# LAUNCHPAD.net
KiCad netlist of a schematic drawn in Altium Designer
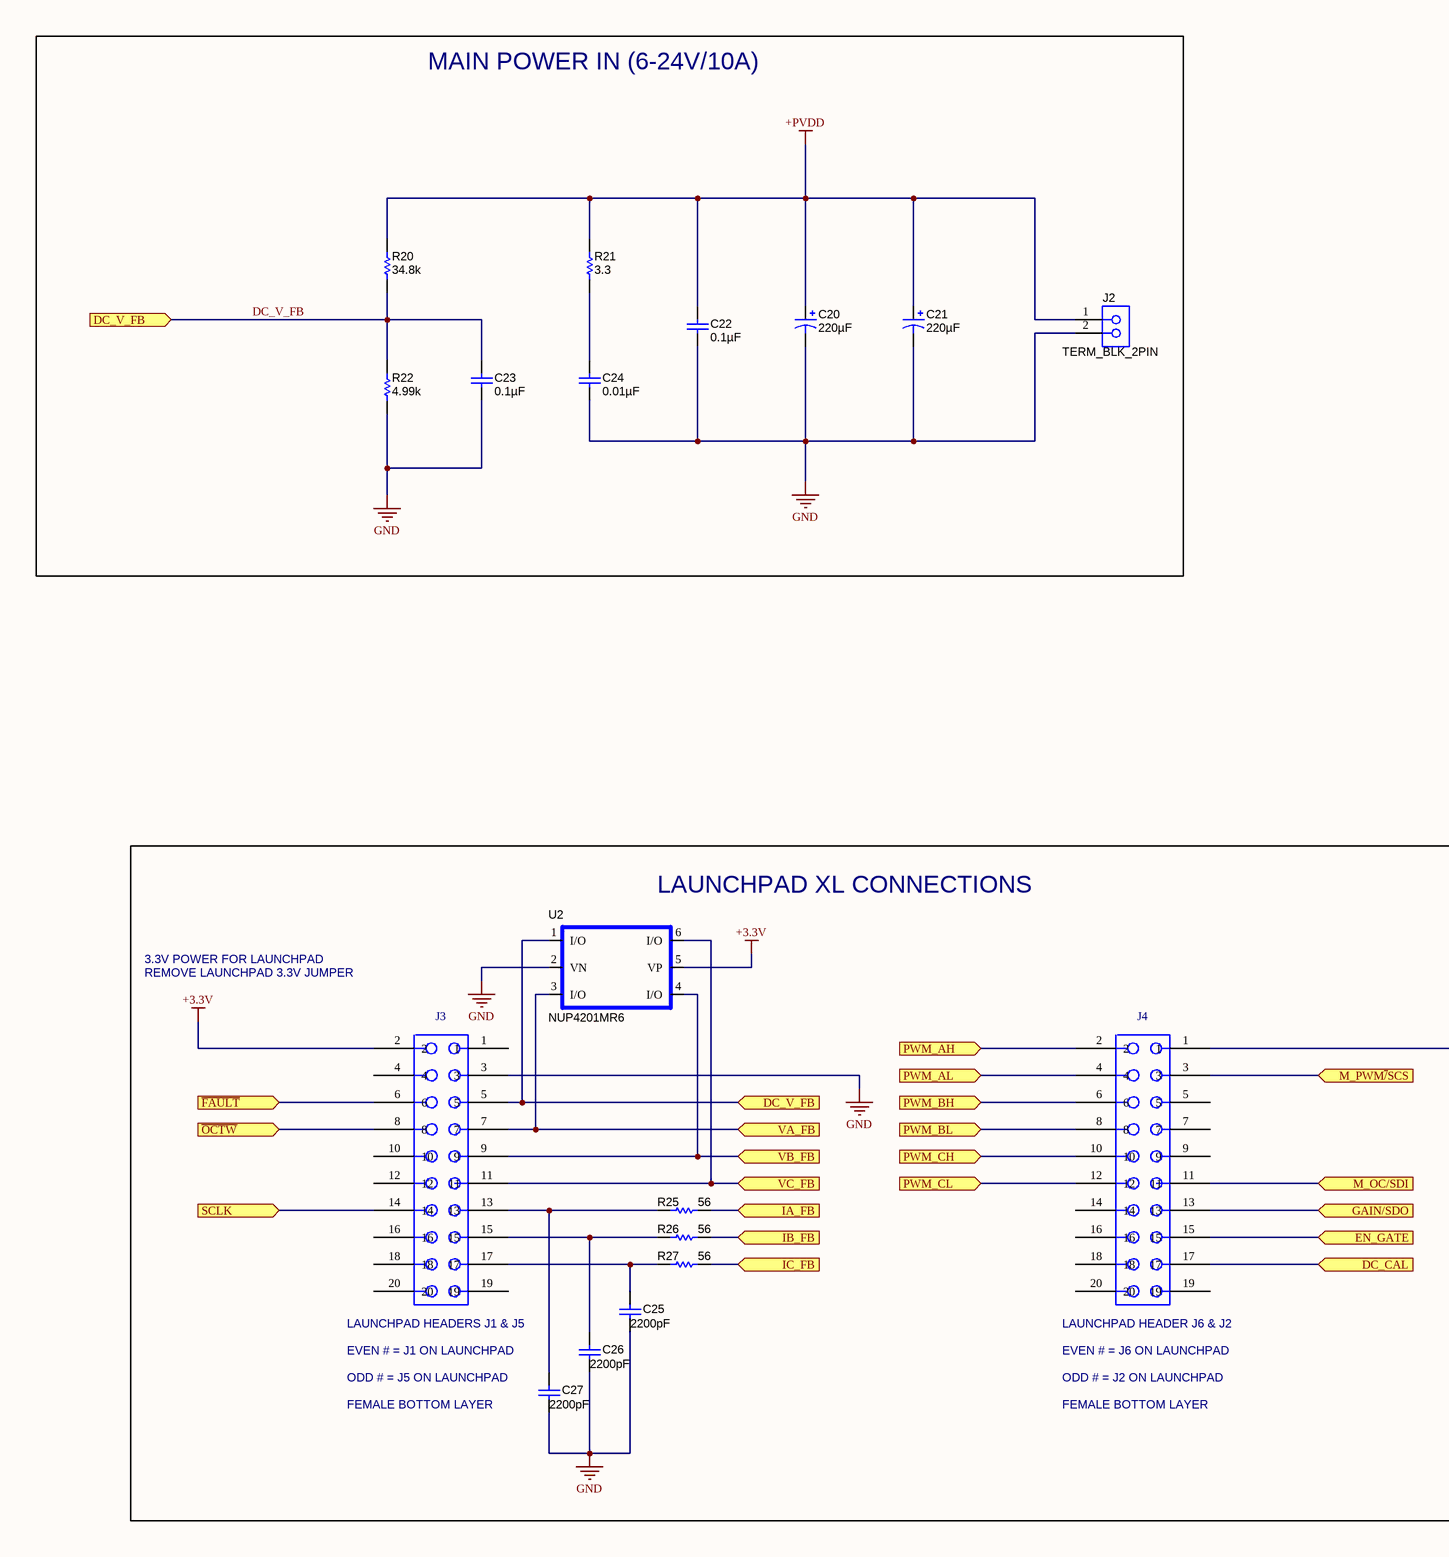
[diagram p0: LAUNCHPAD.SchDoc, left]
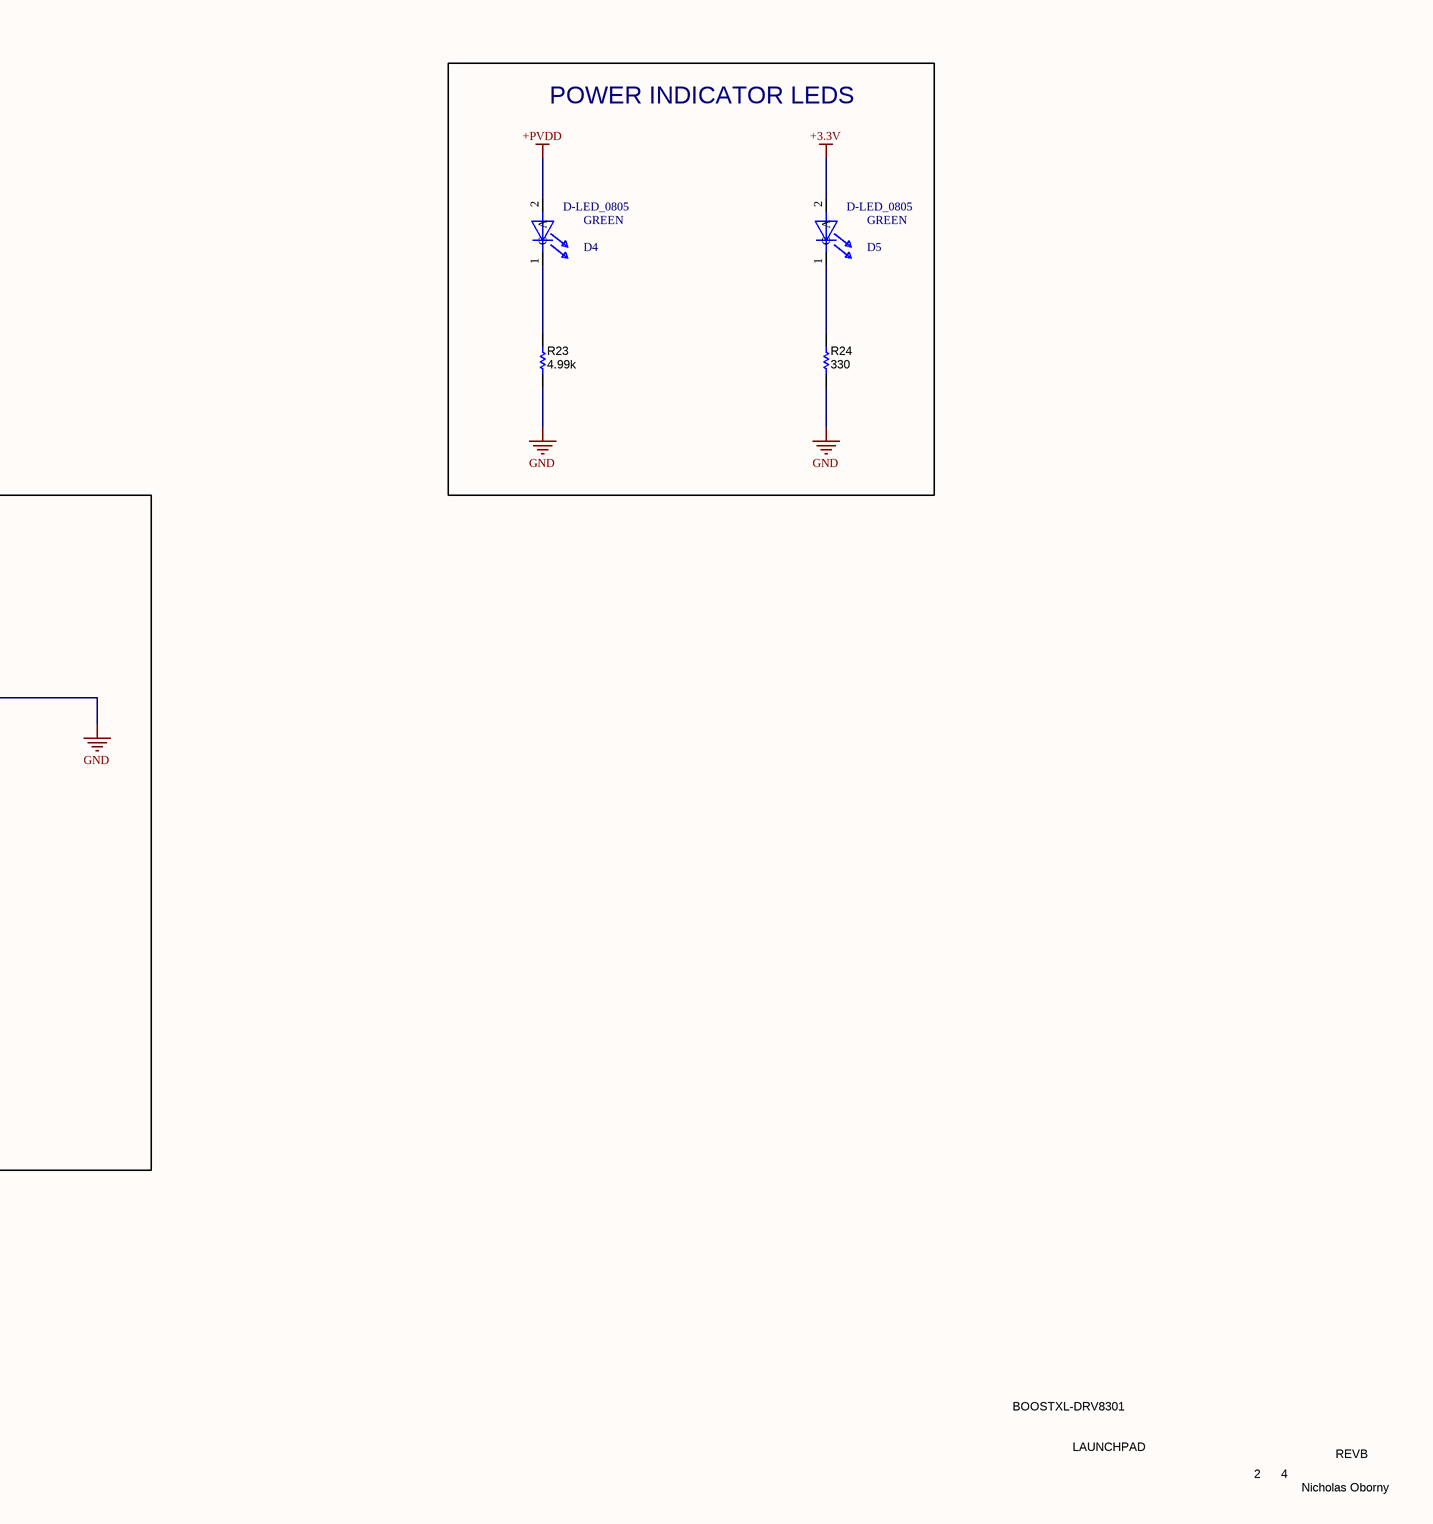
[diagram p1: LAUNCHPAD.SchDoc, right]

(export (version "E")
  (design (tool "Eeschema 10.0.6"))
  (components
    (comp (ref "C20")
      (value "EEE-FC1H221P")
      (footprint "SM_RADIAL_G")
      (description "CAP, AL, 220uF, 50V, +/-20%, 0.3 ohm, SMD")
      (fields
        (field (name "VALUEDISPLAYED") "220µF")
        (field (name "MANUFACTURER") "Panasonic")
        (field (name "PUBLISHER") "Texas Instruments")
      )
      (libsource (lib "Capacitor_Aluminum") (part "EEE-FC1H221P"))
    )
    (comp (ref "C21")
      (value "EEE-FC1H221P")
      (footprint "SM_RADIAL_G")
      (description "CAP, AL, 220uF, 50V, +/-20%, 0.3 ohm, SMD")
      (fields
        (field (name "VALUEDISPLAYED") "220µF")
        (field (name "MANUFACTURER") "Panasonic")
        (field (name "PUBLISHER") "Texas Instruments")
      )
      (libsource (lib "Capacitor_Aluminum") (part "EEE-FC1H221P"))
    )
    (comp (ref "C22")
      (value "GRM188R72A104KA35D")
      (footprint "0603L")
      (description "CAP, CERM, 0.1uF, 100V, +/-10%, X7R, 0603")
      (fields
        (field (name "VALUEDISPLAYED") "0.1µF")
        (field (name "MANUFACTURER") "MuRata")
        (field (name "PUBLISHER") "Texas Instruments")
      )
      (libsource (lib "Capacitor_Ceramic") (part "GRM188R72A104KA35D"))
    )
    (comp (ref "C23")
      (value "C0603C104J4RACTU")
      (footprint "0603L")
      (description "CAP, CERM, 0.1uF, 16V, +/-5%, X7R, 0603")
      (fields
        (field (name "VALUEDISPLAYED") "0.1µF")
        (field (name "MANUFACTURER") "Kemet")
        (field (name "PUBLISHER") "Texas Instruments")
      )
      (libsource (lib "Capacitor_Ceramic") (part "C0603C104J4RACTU"))
    )
    (comp (ref "C24")
      (value "C1608X7R2A103K")
      (footprint "0603L")
      (description "CAP, CERM, 0.01uF, 100V, +/-10%, X7R, 0603")
      (fields
        (field (name "VALUEDISPLAYED") "0.01µF")
        (field (name "MANUFACTURER") "TDK")
        (field (name "PUBLISHER") "Texas Instruments")
      )
      (libsource (lib "Capacitor_Ceramic") (part "C1608X7R2A103K"))
    )
    (comp (ref "C25")
      (value "GRM188R71C222KA01D")
      (footprint "0603L")
      (description "CAP, CERM, 2200pF, 16V, +/-10%, X7R, 0603")
      (fields
        (field (name "VALUEDISPLAYED") "2200pF")
        (field (name "MANUFACTURER") "MuRata")
        (field (name "PUBLISHER") "Texas Instruments")
      )
      (libsource (lib "Capacitor_Ceramic") (part "GRM188R71C222KA01D"))
    )
    (comp (ref "C26")
      (value "GRM188R71C222KA01D")
      (footprint "0603L")
      (description "CAP, CERM, 2200pF, 16V, +/-10%, X7R, 0603")
      (fields
        (field (name "VALUEDISPLAYED") "2200pF")
        (field (name "MANUFACTURER") "MuRata")
        (field (name "PUBLISHER") "Texas Instruments")
      )
      (libsource (lib "Capacitor_Ceramic") (part "GRM188R71C222KA01D"))
    )
    (comp (ref "C27")
      (value "GRM188R71C222KA01D")
      (footprint "0603L")
      (description "CAP, CERM, 2200pF, 16V, +/-10%, X7R, 0603")
      (fields
        (field (name "VALUEDISPLAYED") "2200pF")
        (field (name "MANUFACTURER") "MuRata")
        (field (name "PUBLISHER") "Texas Instruments")
      )
      (libsource (lib "Capacitor_Ceramic") (part "GRM188R71C222KA01D"))
    )
    (comp (ref "D4")
      (value "D-LED_0805")
      (footprint "LED_0805")
      (description "LED THIN 565NM GRN DIFF 0805 SMD")
      (fields
        (field (name "PARTNUMBER") "SML-LXT0805GW-TR")
        (field (name "ALTIUM_VALUE") "GREEN")
        (field (name "MANUFACTURER") "Lumex Opto/Components Inc")
      )
      (libsource (lib "*") (part "D-LED_0805"))
    )
    (comp (ref "D5")
      (value "D-LED_0805")
      (footprint "LED_0805")
      (description "LED THIN 565NM GRN DIFF 0805 SMD")
      (fields
        (field (name "PARTNUMBER") "SML-LXT0805GW-TR")
        (field (name "ALTIUM_VALUE") "GREEN")
        (field (name "MANUFACTURER") "Lumex Opto/Components Inc")
      )
      (libsource (lib "*") (part "D-LED_0805"))
    )
    (comp (ref "J2")
      (value "TERM_BLK_2PIN")
      (footprint "CONN_ED120-2DS")
      (description "TERMINAL BLOCK 5.08MM VERT 2POS")
      (fields
        (field (name "PARTNUMBER") "OSTTA024163")
        (field (name "MANUFACTURER") "On-Shore Technology")
        (field (name "PUBLISHER") "Texas Instruments")
      )
      (libsource (lib "Connectors") (part "ED120/2DS"))
    )
    (comp (ref "J3")
      (value "HEADER_NPTC202KFM")
      (description "CONN RCPT 20POS .100 DL STR SMD")
      (fields (field (name "PARTNUMBER") "89898-310ALF") (field (name "MANUFACTURER") "FCI"))
      (libsource (lib "*") (part "HEADER_NPTC202KFM"))
    )
    (comp (ref "J4")
      (value "HEADER_NPTC202KFM")
      (description "CONN RCPT 20POS .100 DL STR SMD")
      (fields (field (name "PARTNUMBER") "89898-310ALF") (field (name "MANUFACTURER") "FCI"))
      (libsource (lib "*") (part "HEADER_NPTC202KFM"))
    )
    (comp (ref "R20")
      (value "34.8k")
      (footprint "0603L")
      (description "RES, 34.8k ohm, 1%, 0.1W, 0603")
      (fields
        (field (name "PARTNUMBER") "CRCW060334K8FKEA")
        (field (name "MANUFACTURER") "Vishay-Dale")
        (field (name "PUBLISHER") "Texas Instruments")
      )
      (libsource (lib "Resistor_0603") (part "CRCW060334K8FKEA"))
    )
    (comp (ref "R21")
      (value "3.3")
      (footprint "1206L")
      (description "RES, 3.3 ohm, 5%, 0.25W, 1206")
      (fields
        (field (name "PARTNUMBER") "CRCW12063R30JNEA")
        (field (name "MANUFACTURER") "Vishay-Dale")
        (field (name "PUBLISHER") "Texas Instruments")
      )
      (libsource (lib "Resistor_1206") (part "CRCW12063R30JNEA"))
    )
    (comp (ref "R22")
      (value "4.99k")
      (footprint "0603L")
      (description "RES, 4.99k ohm, 1%, 0.1W, 0603")
      (fields
        (field (name "PARTNUMBER") "CRCW06034K99FKEA")
        (field (name "MANUFACTURER") "Vishay-Dale")
        (field (name "PUBLISHER") "Texas Instruments")
      )
      (libsource (lib "Resistor_0603") (part "CRCW06034K99FKEA"))
    )
    (comp (ref "R23")
      (value "4.99k")
      (footprint "0603L")
      (description "RES, 4.99k ohm, 1%, 0.1W, 0603")
      (fields
        (field (name "PARTNUMBER") "CRCW06034K99FKEA")
        (field (name "MANUFACTURER") "Vishay-Dale")
        (field (name "PUBLISHER") "Texas Instruments")
      )
      (libsource (lib "Resistor_0603") (part "CRCW06034K99FKEA"))
    )
    (comp (ref "R24")
      (value "330")
      (footprint "0603L")
      (description "RES, 330 ohm, 5%, 0.1W, 0603")
      (fields
        (field (name "PARTNUMBER") "CRCW0603330RJNEA")
        (field (name "MANUFACTURER") "Vishay-Dale")
        (field (name "PUBLISHER") "Texas Instruments")
      )
      (libsource (lib "Resistor_0603") (part "CRCW0603330RJNEA"))
    )
    (comp (ref "R25")
      (value "56")
      (footprint "0603L")
      (description "RES, 56 ohm, 5%, 0.1W, 0603")
      (fields
        (field (name "PARTNUMBER") "CRCW060356R0JNEA")
        (field (name "MANUFACTURER") "Vishay-Dale")
        (field (name "PUBLISHER") "Texas Instruments")
      )
      (libsource (lib "Resistor_0603") (part "CRCW060356R0JNEA"))
    )
    (comp (ref "R26")
      (value "56")
      (footprint "0603L")
      (description "RES, 56 ohm, 5%, 0.1W, 0603")
      (fields
        (field (name "PARTNUMBER") "CRCW060356R0JNEA")
        (field (name "MANUFACTURER") "Vishay-Dale")
        (field (name "PUBLISHER") "Texas Instruments")
      )
      (libsource (lib "Resistor_0603") (part "CRCW060356R0JNEA"))
    )
    (comp (ref "R27")
      (value "56")
      (footprint "0603L")
      (description "RES, 56 ohm, 5%, 0.1W, 0603")
      (fields
        (field (name "PARTNUMBER") "CRCW060356R0JNEA")
        (field (name "MANUFACTURER") "Vishay-Dale")
        (field (name "PUBLISHER") "Texas Instruments")
      )
      (libsource (lib "Resistor_0603") (part "CRCW060356R0JNEA"))
    )
    (comp (ref "U2")
      (value "NUP4201MR6")
      (footprint "SOT23-6")
      (description "IC,  500w 6v, Transient Voltage  Suppressors")
      (fields (field (name "MANUFACTURER") "On Semi"))
      (libsource (lib "PADSlegacy_PMP") (part "NUP4201MR6"))
    )
  )
  (nets
    (net (code "1") (name "+3.3V") (class "Default")
      (node (ref "D5") (pin "2") (pinfunction "A_2") (pintype "passive"))
      (node (ref "J3") (pin "2") (pinfunction "2_2") (pintype "passive"))
      (node (ref "U2") (pin "5") (pinfunction "VP_5") (pintype "passive"))
    )
    (net (code "2") (name "+PVDD") (class "Default")
      (node (ref "C20") (pin "1") (pinfunction "+_1") (pintype "passive"))
      (node (ref "C21") (pin "1") (pinfunction "+_1") (pintype "passive"))
      (node (ref "C22") (pin "1") (pinfunction "1_1") (pintype "passive"))
      (node (ref "D4") (pin "2") (pinfunction "A_2") (pintype "passive"))
      (node (ref "J2") (pin "1") (pinfunction "1_1") (pintype "passive"))
      (node (ref "R20") (pin "2") (pinfunction "2_2") (pintype "passive"))
      (node (ref "R21") (pin "2") (pinfunction "2_2") (pintype "passive"))
    )
    (net (code "3") (name "/DC_CAL") (class "Default")
      (node (ref "J4") (pin "17") (pinfunction "17_17") (pintype "passive"))
    )
    (net (code "4") (name "/DC_V_FB") (class "Default")
      (node (ref "C23") (pin "1") (pinfunction "1_1") (pintype "passive"))
      (node (ref "J3") (pin "5") (pinfunction "5_5") (pintype "passive"))
      (node (ref "R20") (pin "1") (pinfunction "1_1") (pintype "passive"))
      (node (ref "R22") (pin "2") (pinfunction "2_2") (pintype "passive"))
      (node (ref "U2") (pin "1") (pinfunction "I/O_1") (pintype "passive"))
    )
    (net (code "5") (name "/EN_GATE") (class "Default")
      (node (ref "J4") (pin "15") (pinfunction "15_15") (pintype "passive"))
    )
    (net (code "6") (name "/FAULT") (class "Default")
      (node (ref "J3") (pin "6") (pinfunction "6_6") (pintype "passive"))
    )
    (net (code "7") (name "/GAIN{slash}SDO") (class "Default")
      (node (ref "J4") (pin "13") (pinfunction "13_13") (pintype "passive"))
    )
    (net (code "8") (name "/IA_FB") (class "Default")
      (node (ref "R25") (pin "2") (pinfunction "2_2") (pintype "passive"))
    )
    (net (code "9") (name "/IB_FB") (class "Default")
      (node (ref "R26") (pin "2") (pinfunction "2_2") (pintype "passive"))
    )
    (net (code "10") (name "/IC_FB") (class "Default")
      (node (ref "R27") (pin "2") (pinfunction "2_2") (pintype "passive"))
    )
    (net (code "11") (name "/M_OC{slash}SDI") (class "Default")
      (node (ref "J4") (pin "11") (pinfunction "11_11") (pintype "passive"))
    )
    (net (code "12") (name "/M_PWM~{{slash}}SCS") (class "Default")
      (node (ref "J4") (pin "3") (pinfunction "3_3") (pintype "passive"))
    )
    (net (code "13") (name "/OCTW") (class "Default")
      (node (ref "J3") (pin "8") (pinfunction "8_8") (pintype "passive"))
    )
    (net (code "14") (name "/PWM_AH") (class "Default")
      (node (ref "J4") (pin "2") (pinfunction "2_2") (pintype "passive"))
    )
    (net (code "15") (name "/PWM_AL") (class "Default")
      (node (ref "J4") (pin "4") (pinfunction "4_4") (pintype "passive"))
    )
    (net (code "16") (name "/PWM_BH") (class "Default")
      (node (ref "J4") (pin "6") (pinfunction "6_6") (pintype "passive"))
    )
    (net (code "17") (name "/PWM_BL") (class "Default")
      (node (ref "J4") (pin "8") (pinfunction "8_8") (pintype "passive"))
    )
    (net (code "18") (name "/PWM_CH") (class "Default")
      (node (ref "J4") (pin "10") (pinfunction "10_10") (pintype "passive"))
    )
    (net (code "19") (name "/PWM_CL") (class "Default")
      (node (ref "J4") (pin "12") (pinfunction "12_12") (pintype "passive"))
    )
    (net (code "20") (name "/SCLK") (class "Default")
      (node (ref "J3") (pin "14") (pinfunction "14_14") (pintype "passive"))
    )
    (net (code "21") (name "/VA_FB") (class "Default")
      (node (ref "J3") (pin "7") (pinfunction "7_7") (pintype "passive"))
      (node (ref "U2") (pin "3") (pinfunction "I/O_3") (pintype "passive"))
    )
    (net (code "22") (name "/VB_FB") (class "Default")
      (node (ref "J3") (pin "9") (pinfunction "9_9") (pintype "passive"))
      (node (ref "U2") (pin "4") (pinfunction "I/O_4") (pintype "passive"))
    )
    (net (code "23") (name "/VC_FB") (class "Default")
      (node (ref "J3") (pin "11") (pinfunction "11_11") (pintype "passive"))
      (node (ref "U2") (pin "6") (pinfunction "I/O_6") (pintype "passive"))
    )
    (net (code "24") (name "GND") (class "Default")
      (node (ref "C20") (pin "2") (pinfunction "-_2") (pintype "passive"))
      (node (ref "C21") (pin "2") (pinfunction "-_2") (pintype "passive"))
      (node (ref "C22") (pin "2") (pinfunction "2_2") (pintype "passive"))
      (node (ref "C23") (pin "2") (pinfunction "2_2") (pintype "passive"))
      (node (ref "C24") (pin "2") (pinfunction "2_2") (pintype "passive"))
      (node (ref "C25") (pin "2") (pinfunction "2_2") (pintype "passive"))
      (node (ref "C26") (pin "2") (pinfunction "2_2") (pintype "passive"))
      (node (ref "C27") (pin "2") (pinfunction "2_2") (pintype "passive"))
      (node (ref "J2") (pin "2") (pinfunction "2_2") (pintype "passive"))
      (node (ref "J3") (pin "3") (pinfunction "3_3") (pintype "passive"))
      (node (ref "J4") (pin "1") (pinfunction "1_1") (pintype "passive"))
      (node (ref "R22") (pin "1") (pinfunction "1_1") (pintype "passive"))
      (node (ref "R23") (pin "1") (pinfunction "1_1") (pintype "passive"))
      (node (ref "R24") (pin "1") (pinfunction "1_1") (pintype "passive"))
      (node (ref "U2") (pin "2") (pinfunction "VN_2") (pintype "passive"))
    )
    (net (code "25") (name "Net-(C24-Pad1)") (class "Default")
      (node (ref "C24") (pin "1") (pinfunction "1_1") (pintype "passive"))
      (node (ref "R21") (pin "1") (pinfunction "1_1") (pintype "passive"))
    )
    (net (code "26") (name "Net-(C25-Pad1)") (class "Default")
      (node (ref "C25") (pin "1") (pinfunction "1_1") (pintype "passive"))
      (node (ref "J3") (pin "17") (pinfunction "17_17") (pintype "passive"))
      (node (ref "R27") (pin "1") (pinfunction "1_1") (pintype "passive"))
    )
    (net (code "27") (name "Net-(C26-Pad1)") (class "Default")
      (node (ref "C26") (pin "1") (pinfunction "1_1") (pintype "passive"))
      (node (ref "J3") (pin "15") (pinfunction "15_15") (pintype "passive"))
      (node (ref "R26") (pin "1") (pinfunction "1_1") (pintype "passive"))
    )
    (net (code "28") (name "Net-(C27-Pad1)") (class "Default")
      (node (ref "C27") (pin "1") (pinfunction "1_1") (pintype "passive"))
      (node (ref "J3") (pin "13") (pinfunction "13_13") (pintype "passive"))
      (node (ref "R25") (pin "1") (pinfunction "1_1") (pintype "passive"))
    )
    (net (code "29") (name "Net-(D4-C)") (class "Default")
      (node (ref "D4") (pin "1") (pinfunction "C_1") (pintype "passive"))
      (node (ref "R23") (pin "2") (pinfunction "2_2") (pintype "passive"))
    )
    (net (code "30") (name "Net-(D5-C)") (class "Default")
      (node (ref "D5") (pin "1") (pinfunction "C_1") (pintype "passive"))
      (node (ref "R24") (pin "2") (pinfunction "2_2") (pintype "passive"))
    )
    (net (code "31") (name "unconnected-(J3-Pad1)") (class "Default")
      (node (ref "J3") (pin "1") (pinfunction "1_1") (pintype "passive"))
    )
    (net (code "32") (name "unconnected-(J3-Pad4)") (class "Default")
      (node (ref "J3") (pin "4") (pinfunction "4_4") (pintype "passive"))
    )
    (net (code "33") (name "unconnected-(J3-Pad10)") (class "Default")
      (node (ref "J3") (pin "10") (pinfunction "10_10") (pintype "passive"))
    )
    (net (code "34") (name "unconnected-(J3-Pad12)") (class "Default")
      (node (ref "J3") (pin "12") (pinfunction "12_12") (pintype "passive"))
    )
    (net (code "35") (name "unconnected-(J3-Pad16)") (class "Default")
      (node (ref "J3") (pin "16") (pinfunction "16_16") (pintype "passive"))
    )
    (net (code "36") (name "unconnected-(J3-Pad18)") (class "Default")
      (node (ref "J3") (pin "18") (pinfunction "18_18") (pintype "passive"))
    )
    (net (code "37") (name "unconnected-(J3-Pad19)") (class "Default")
      (node (ref "J3") (pin "19") (pinfunction "19_19") (pintype "passive"))
    )
    (net (code "38") (name "unconnected-(J3-Pad20)") (class "Default")
      (node (ref "J3") (pin "20") (pinfunction "20_20") (pintype "passive"))
    )
    (net (code "39") (name "unconnected-(J4-Pad5)") (class "Default")
      (node (ref "J4") (pin "5") (pinfunction "5_5") (pintype "passive"))
    )
    (net (code "40") (name "unconnected-(J4-Pad7)") (class "Default")
      (node (ref "J4") (pin "7") (pinfunction "7_7") (pintype "passive"))
    )
    (net (code "41") (name "unconnected-(J4-Pad9)") (class "Default")
      (node (ref "J4") (pin "9") (pinfunction "9_9") (pintype "passive"))
    )
    (net (code "42") (name "unconnected-(J4-Pad14)") (class "Default")
      (node (ref "J4") (pin "14") (pinfunction "14_14") (pintype "passive"))
    )
    (net (code "43") (name "unconnected-(J4-Pad16)") (class "Default")
      (node (ref "J4") (pin "16") (pinfunction "16_16") (pintype "passive"))
    )
    (net (code "44") (name "unconnected-(J4-Pad18)") (class "Default")
      (node (ref "J4") (pin "18") (pinfunction "18_18") (pintype "passive"))
    )
    (net (code "45") (name "unconnected-(J4-Pad19)") (class "Default")
      (node (ref "J4") (pin "19") (pinfunction "19_19") (pintype "passive"))
    )
    (net (code "46") (name "unconnected-(J4-Pad20)") (class "Default")
      (node (ref "J4") (pin "20") (pinfunction "20_20") (pintype "passive"))
    )
  )
)
